# DISPLAY_IT3_1.net
KiCad netlist of a schematic drawn in EAGLE
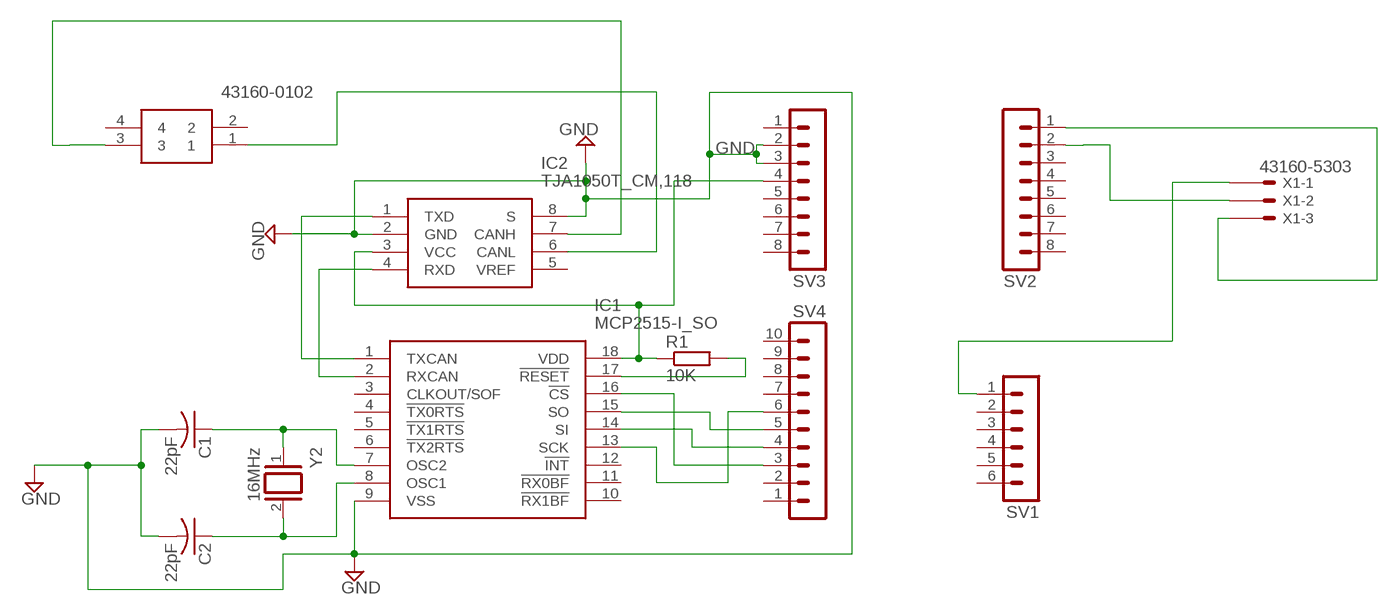
[diagram p0: schematic, sheet 1]

(export (version "E")
  (design (tool "Eeschema 10.0.6"))
  (components
    (comp (ref "C1")
      (value "22pF")
      (footprint "eagle-import:C025-024X044")
      (libsource (lib "eagle-import") (part "C-US025-024X044"))
    )
    (comp (ref "C2")
      (value "22pF")
      (footprint "eagle-import:C025-024X044")
      (libsource (lib "eagle-import") (part "C-US025-024X044"))
    )
    (comp (ref "DIFF_N")
      (value "43160-0102")
      (footprint "eagle-import:431600102")
      (fields (field (name "MOUSER_PART_NUMBER") "538-43160-0102"))
      (libsource (lib "eagle-import") (part "43160-0102"))
    )
    (comp (ref "IC1")
      (value "MCP2515-I_SO")
      (footprint "eagle-import:SOIC127P1030X265-18N")
      (fields
        (field (name "ARROW_PART_NUMBER") "MCP2515-I/SO")
        (field (name "MOUSER_PART_NUMBER") "579-MCP2515-I/SO")
      )
      (libsource (lib "eagle-import") (part "MCP2515-I_SO"))
    )
    (comp (ref "IC2")
      (value "TJA1050T_CM,118")
      (footprint "eagle-import:SOIC127P600X175-8N")
      (fields
        (field (name "ARROW_PART_NUMBER") "TJA1050T/CM,118")
        (field (name "MOUSER_PART_NUMBER") "771-TJA1050T/CM118")
      )
      (libsource (lib "eagle-import") (part "TJA1050T_CM,118"))
    )
    (comp (ref "R1")
      (value "10K")
      (footprint "eagle-import:0204_7")
      (libsource (lib "eagle-import") (part "R-EU_0204/7"))
    )
    (comp (ref "SV1")
      (value "MA06-1")
      (footprint "eagle-import:MA06-1")
      (libsource (lib "eagle-import") (part "MA06-1"))
    )
    (comp (ref "SV2")
      (value "MA08-1")
      (footprint "eagle-import:MA08-1")
      (libsource (lib "eagle-import") (part "MA08-1"))
    )
    (comp (ref "SV3")
      (value "MA08-1")
      (footprint "eagle-import:MA08-1")
      (libsource (lib "eagle-import") (part "MA08-1"))
    )
    (comp (ref "SV4")
      (value "MA10-1")
      (footprint "eagle-import:MA10-1")
      (libsource (lib "eagle-import") (part "MA10-1"))
    )
    (comp (ref "X1")
      (value "43160-5303")
      (footprint "eagle-import:43160-XX03")
      (fields (field (name "MF") "MOLEX"))
      (libsource (lib "eagle-import") (part "43160-0353"))
    )
    (comp (ref "Y2")
      (value "16MHz")
      (footprint "eagle-import:QS")
      (libsource (lib "eagle-import") (part "XTAL/S"))
    )
  )
  (nets
    (net (code "1") (name "GND") (class "Default")
      (node (ref "C1") (pin "2") (pinfunction "2_2") (pintype "passive"))
      (node (ref "C2") (pin "2") (pinfunction "2_2") (pintype "passive"))
      (node (ref "IC1") (pin "9") (pinfunction "VSS_9") (pintype "bidirectional"))
      (node (ref "IC2") (pin "2") (pinfunction "GND_2") (pintype "bidirectional"))
      (node (ref "IC2") (pin "8") (pinfunction "S_8") (pintype "bidirectional"))
      (node (ref "SV3") (pin "2") (pinfunction "2_2") (pintype "passive"))
      (node (ref "SV3") (pin "3") (pinfunction "3_3") (pintype "passive"))
    )
    (net (code "2") (name "Net-(IC1-OSC1)") (class "Default")
      (node (ref "C2") (pin "1") (pinfunction "1_1") (pintype "passive"))
      (node (ref "IC1") (pin "8") (pinfunction "OSC1_8") (pintype "bidirectional"))
      (node (ref "Y2") (pin "2") (pinfunction "2_2") (pintype "passive"))
    )
    (net (code "3") (name "Net-(IC1-OSC2)") (class "Default")
      (node (ref "C1") (pin "1") (pinfunction "1_1") (pintype "passive"))
      (node (ref "IC1") (pin "7") (pinfunction "OSC2_7") (pintype "bidirectional"))
      (node (ref "Y2") (pin "1") (pinfunction "1_1") (pintype "passive"))
    )
    (net (code "4") (name "Net-(IC1-RXCAN)") (class "Default")
      (node (ref "IC1") (pin "2") (pinfunction "RXCAN_2") (pintype "bidirectional"))
      (node (ref "IC2") (pin "4") (pinfunction "RXD_4") (pintype "bidirectional"))
    )
    (net (code "5") (name "Net-(IC1-SCK)") (class "Default")
      (node (ref "IC1") (pin "13") (pinfunction "SCK_13") (pintype "bidirectional"))
      (node (ref "SV4") (pin "6") (pinfunction "6_6") (pintype "passive"))
    )
    (net (code "6") (name "Net-(IC1-SI)") (class "Default")
      (node (ref "IC1") (pin "14") (pinfunction "SI_14") (pintype "bidirectional"))
      (node (ref "SV4") (pin "4") (pinfunction "4_4") (pintype "passive"))
    )
    (net (code "7") (name "Net-(IC1-SO)") (class "Default")
      (node (ref "IC1") (pin "15") (pinfunction "SO_15") (pintype "bidirectional"))
      (node (ref "SV4") (pin "5") (pinfunction "5_5") (pintype "passive"))
    )
    (net (code "8") (name "Net-(IC1-TXCAN)") (class "Default")
      (node (ref "IC1") (pin "1") (pinfunction "TXCAN_1") (pintype "bidirectional"))
      (node (ref "IC2") (pin "1") (pinfunction "TXD_1") (pintype "bidirectional"))
    )
    (net (code "9") (name "Net-(IC1-VDD)") (class "Default")
      (node (ref "IC1") (pin "18") (pinfunction "VDD_18") (pintype "bidirectional"))
      (node (ref "IC2") (pin "3") (pinfunction "VCC_3") (pintype "bidirectional"))
      (node (ref "R1") (pin "1") (pinfunction "1_1") (pintype "passive"))
      (node (ref "SV3") (pin "4") (pinfunction "4_4") (pintype "passive"))
    )
    (net (code "10") (name "Net-(IC1-~{CS})") (class "Default")
      (node (ref "IC1") (pin "16") (pinfunction "~{CS}_16") (pintype "bidirectional"))
      (node (ref "SV4") (pin "3") (pinfunction "3_3") (pintype "passive"))
    )
    (net (code "11") (name "Net-(IC1-~{RESET})") (class "Default")
      (node (ref "IC1") (pin "17") (pinfunction "~{RESET}_17") (pintype "bidirectional"))
      (node (ref "R1") (pin "2") (pinfunction "2_2") (pintype "passive"))
    )
    (net (code "12") (name "Net-(IC2-CANH)") (class "Default")
      (node (ref "DIFF_N") (pin "3") (pinfunction "3_3") (pintype "bidirectional"))
      (node (ref "IC2") (pin "7") (pinfunction "CANH_7") (pintype "bidirectional"))
    )
    (net (code "13") (name "Net-(IC2-CANL)") (class "Default")
      (node (ref "DIFF_N") (pin "1") (pinfunction "1_1") (pintype "bidirectional"))
      (node (ref "IC2") (pin "6") (pinfunction "CANL_6") (pintype "bidirectional"))
    )
    (net (code "14") (name "Net-(SV1-Pad1)") (class "Default")
      (node (ref "SV1") (pin "1") (pinfunction "1_1") (pintype "passive"))
      (node (ref "X1") (pin "1@1") (pinfunction "S_1@1") (pintype "passive"))
    )
    (net (code "15") (name "Net-(SV2-Pad1)") (class "Default")
      (node (ref "SV2") (pin "1") (pinfunction "1_1") (pintype "passive"))
      (node (ref "X1") (pin "3@1") (pinfunction "S_3@1") (pintype "passive"))
    )
    (net (code "16") (name "Net-(SV2-Pad2)") (class "Default")
      (node (ref "SV2") (pin "2") (pinfunction "2_2") (pintype "passive"))
      (node (ref "X1") (pin "2@1") (pinfunction "S_2@1") (pintype "passive"))
    )
    (net (code "17") (name "unconnected-(DIFF_N-Pad2)") (class "Default")
      (node (ref "DIFF_N") (pin "2") (pinfunction "2_2") (pintype "bidirectional"))
    )
    (net (code "18") (name "unconnected-(DIFF_N-Pad4)") (class "Default")
      (node (ref "DIFF_N") (pin "4") (pinfunction "4_4") (pintype "bidirectional"))
    )
    (net (code "19") (name "unconnected-(IC1-CLKOUT{slash}SOF-Pad3)") (class "Default")
      (node (ref "IC1") (pin "3") (pinfunction "CLKOUT/SOF_3") (pintype "bidirectional"))
    )
    (net (code "20") (name "unconnected-(IC1-~{INT}-Pad12)") (class "Default")
      (node (ref "IC1") (pin "12") (pinfunction "~{INT}_12") (pintype "bidirectional"))
    )
    (net (code "21") (name "unconnected-(IC1-~{RX0BF}-Pad11)") (class "Default")
      (node (ref "IC1") (pin "11") (pinfunction "~{RX0BF}_11") (pintype "bidirectional"))
    )
    (net (code "22") (name "unconnected-(IC1-~{RX1BF}-Pad10)") (class "Default")
      (node (ref "IC1") (pin "10") (pinfunction "~{RX1BF}_10") (pintype "bidirectional"))
    )
    (net (code "23") (name "unconnected-(IC1-~{TX0RTS}-Pad4)") (class "Default")
      (node (ref "IC1") (pin "4") (pinfunction "~{TX0RTS}_4") (pintype "bidirectional"))
    )
    (net (code "24") (name "unconnected-(IC1-~{TX1RTS}-Pad5)") (class "Default")
      (node (ref "IC1") (pin "5") (pinfunction "~{TX1RTS}_5") (pintype "bidirectional"))
    )
    (net (code "25") (name "unconnected-(IC1-~{TX2RTS}-Pad6)") (class "Default")
      (node (ref "IC1") (pin "6") (pinfunction "~{TX2RTS}_6") (pintype "bidirectional"))
    )
    (net (code "26") (name "unconnected-(IC2-VREF-Pad5)") (class "Default")
      (node (ref "IC2") (pin "5") (pinfunction "VREF_5") (pintype "bidirectional"))
    )
    (net (code "27") (name "unconnected-(SV1-Pad2)") (class "Default")
      (node (ref "SV1") (pin "2") (pinfunction "2_2") (pintype "passive"))
    )
    (net (code "28") (name "unconnected-(SV1-Pad3)") (class "Default")
      (node (ref "SV1") (pin "3") (pinfunction "3_3") (pintype "passive"))
    )
    (net (code "29") (name "unconnected-(SV1-Pad4)") (class "Default")
      (node (ref "SV1") (pin "4") (pinfunction "4_4") (pintype "passive"))
    )
    (net (code "30") (name "unconnected-(SV1-Pad5)") (class "Default")
      (node (ref "SV1") (pin "5") (pinfunction "5_5") (pintype "passive"))
    )
    (net (code "31") (name "unconnected-(SV1-Pad6)") (class "Default")
      (node (ref "SV1") (pin "6") (pinfunction "6_6") (pintype "passive"))
    )
    (net (code "32") (name "unconnected-(SV2-Pad3)") (class "Default")
      (node (ref "SV2") (pin "3") (pinfunction "3_3") (pintype "passive"))
    )
    (net (code "33") (name "unconnected-(SV2-Pad4)") (class "Default")
      (node (ref "SV2") (pin "4") (pinfunction "4_4") (pintype "passive"))
    )
    (net (code "34") (name "unconnected-(SV2-Pad5)") (class "Default")
      (node (ref "SV2") (pin "5") (pinfunction "5_5") (pintype "passive"))
    )
    (net (code "35") (name "unconnected-(SV2-Pad6)") (class "Default")
      (node (ref "SV2") (pin "6") (pinfunction "6_6") (pintype "passive"))
    )
    (net (code "36") (name "unconnected-(SV2-Pad7)") (class "Default")
      (node (ref "SV2") (pin "7") (pinfunction "7_7") (pintype "passive"))
    )
    (net (code "37") (name "unconnected-(SV2-Pad8)") (class "Default")
      (node (ref "SV2") (pin "8") (pinfunction "8_8") (pintype "passive"))
    )
    (net (code "38") (name "unconnected-(SV3-Pad1)") (class "Default")
      (node (ref "SV3") (pin "1") (pinfunction "1_1") (pintype "passive"))
    )
    (net (code "39") (name "unconnected-(SV3-Pad5)") (class "Default")
      (node (ref "SV3") (pin "5") (pinfunction "5_5") (pintype "passive"))
    )
    (net (code "40") (name "unconnected-(SV3-Pad6)") (class "Default")
      (node (ref "SV3") (pin "6") (pinfunction "6_6") (pintype "passive"))
    )
    (net (code "41") (name "unconnected-(SV3-Pad7)") (class "Default")
      (node (ref "SV3") (pin "7") (pinfunction "7_7") (pintype "passive"))
    )
    (net (code "42") (name "unconnected-(SV3-Pad8)") (class "Default")
      (node (ref "SV3") (pin "8") (pinfunction "8_8") (pintype "passive"))
    )
    (net (code "43") (name "unconnected-(SV4-Pad1)") (class "Default")
      (node (ref "SV4") (pin "1") (pinfunction "1_1") (pintype "passive"))
    )
    (net (code "44") (name "unconnected-(SV4-Pad2)") (class "Default")
      (node (ref "SV4") (pin "2") (pinfunction "2_2") (pintype "passive"))
    )
    (net (code "45") (name "unconnected-(SV4-Pad7)") (class "Default")
      (node (ref "SV4") (pin "7") (pinfunction "7_7") (pintype "passive"))
    )
    (net (code "46") (name "unconnected-(SV4-Pad8)") (class "Default")
      (node (ref "SV4") (pin "8") (pinfunction "8_8") (pintype "passive"))
    )
    (net (code "47") (name "unconnected-(SV4-Pad9)") (class "Default")
      (node (ref "SV4") (pin "9") (pinfunction "9_9") (pintype "passive"))
    )
    (net (code "48") (name "unconnected-(SV4-Pad10)") (class "Default")
      (node (ref "SV4") (pin "10") (pinfunction "10_10") (pintype "passive"))
    )
    (net (code "49") (name "unconnected-(X1A-S-Pad1@2)") (class "Default")
      (node (ref "X1") (pin "1@2") (pinfunction "S_1@2") (pintype "passive"))
    )
    (net (code "50") (name "unconnected-(X1B-S-Pad2@2)") (class "Default")
      (node (ref "X1") (pin "2@2") (pinfunction "S_2@2") (pintype "passive"))
    )
    (net (code "51") (name "unconnected-(X1C-S-Pad3@2)") (class "Default")
      (node (ref "X1") (pin "3@2") (pinfunction "S_3@2") (pintype "passive"))
    )
  )
)
